# Beetech_NanoEvery.net
KiCad netlist of a schematic drawn in Altium Designer
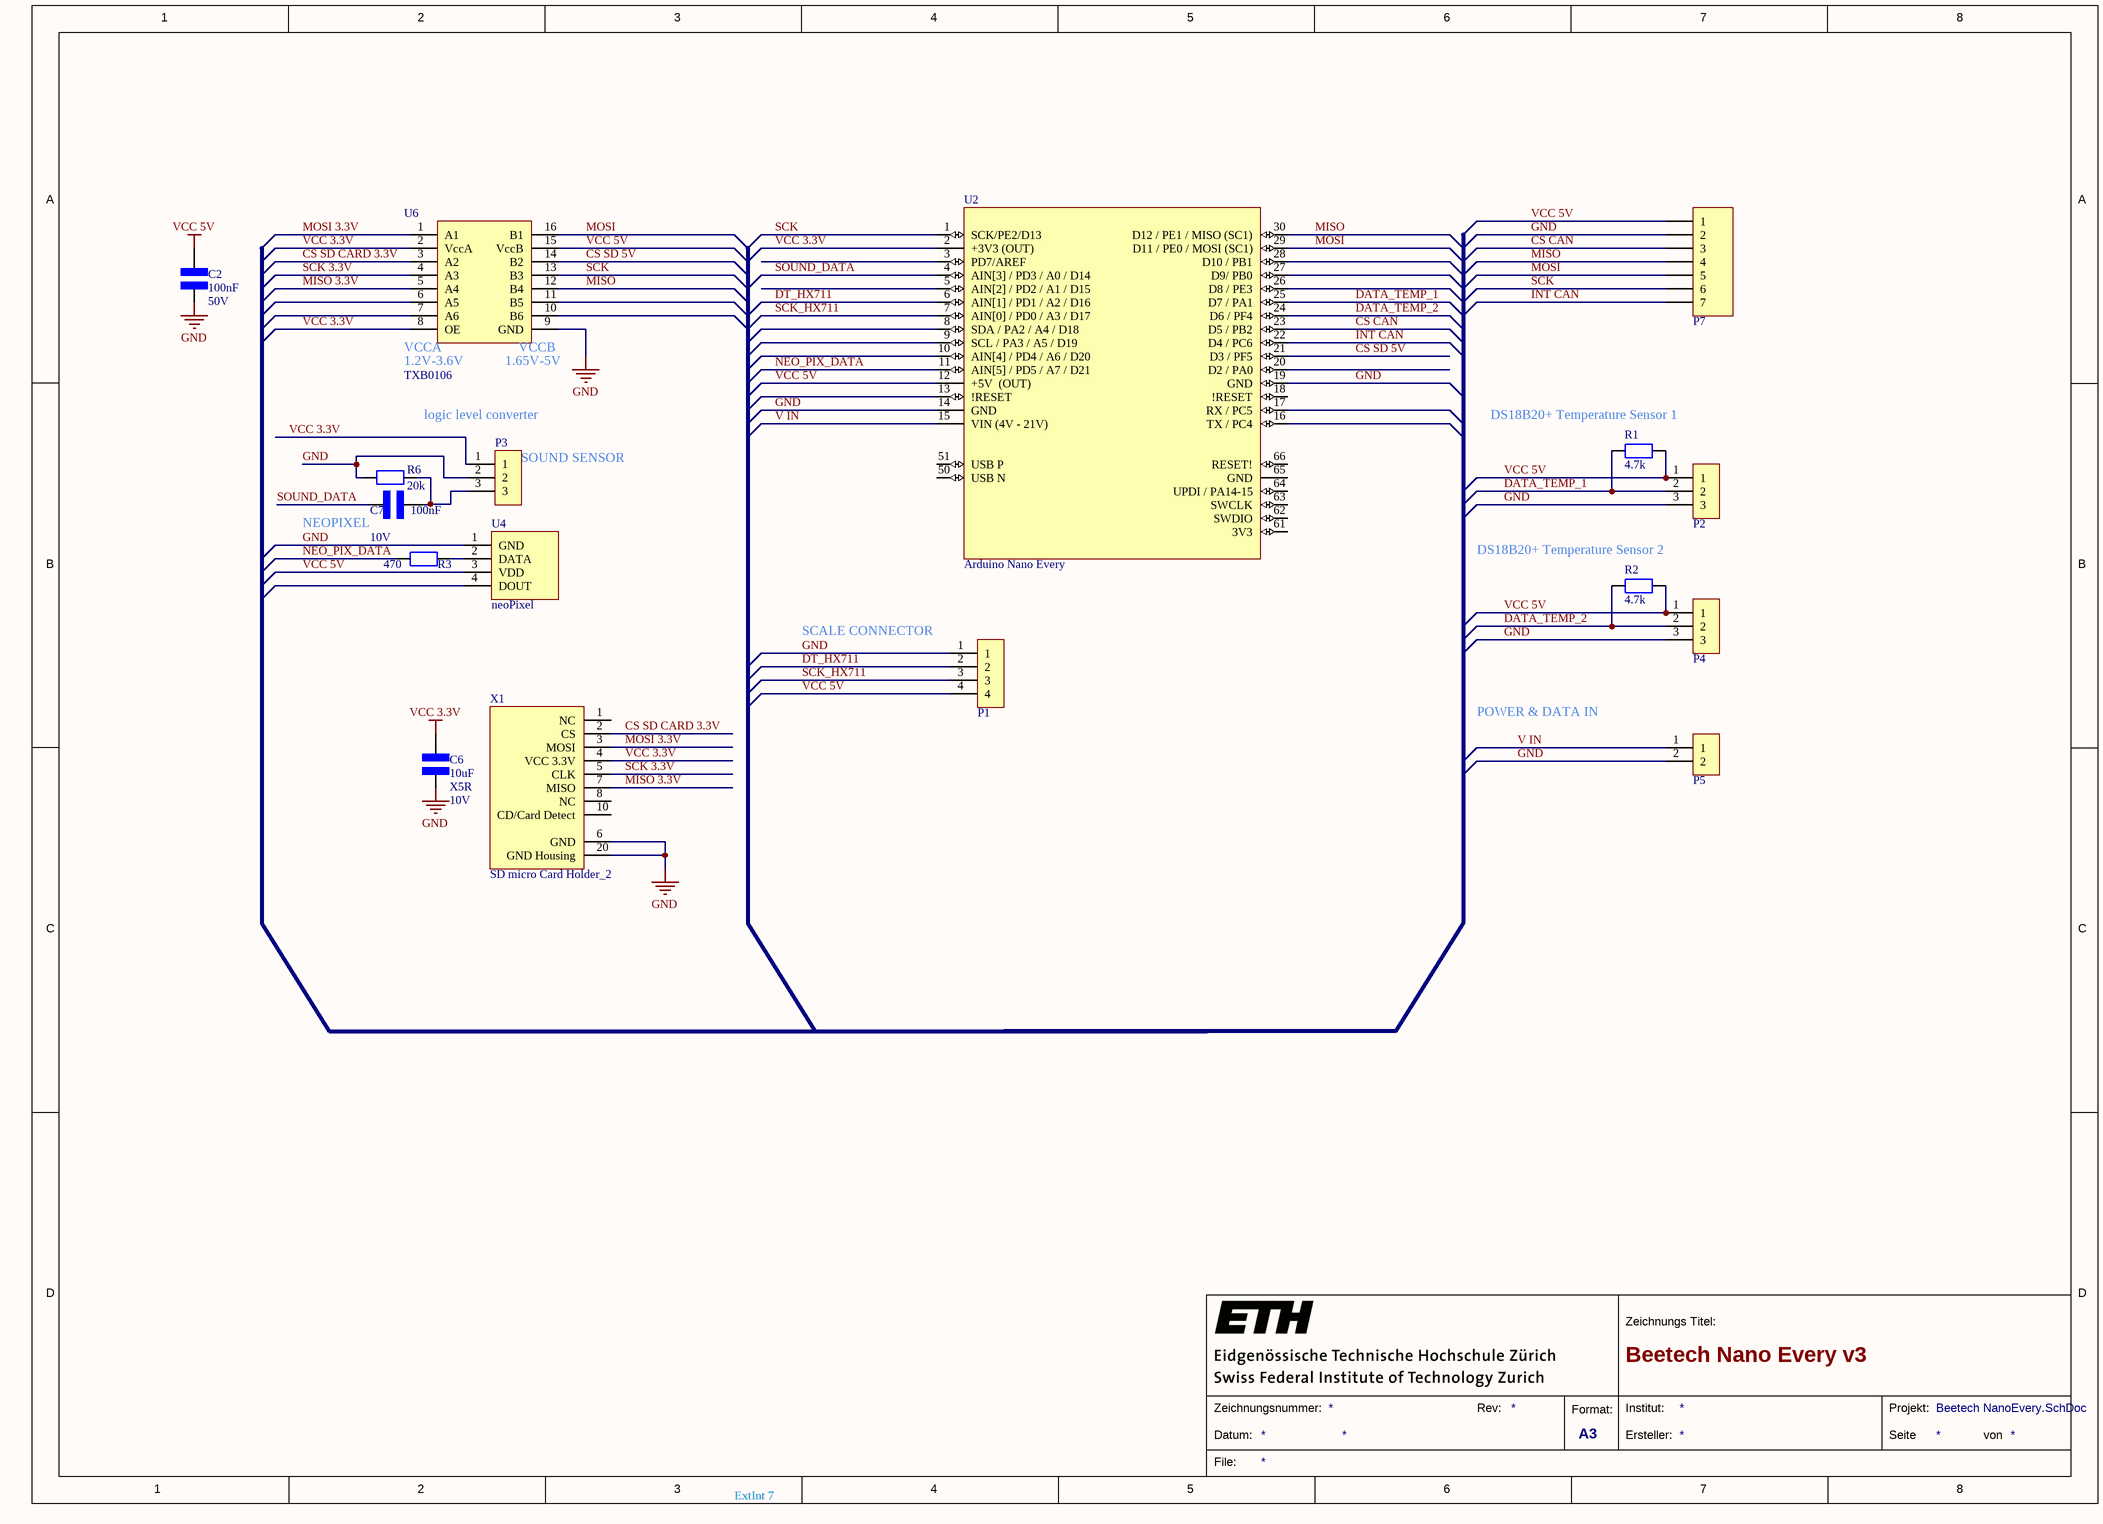
[diagram p0: Beetech NanoEvery.SchDoc]

(export (version "E")
  (design (tool "Eeschema 10.0.6"))
  (components
    (comp (ref "C2")
      (value "100nF")
      (footprint "CAP 0603")
      (description "C CERAMIC SMD")
      (fields (field (name "UMAX") "50V") (field (name "Comment") "100nF 0603_1"))
      (libsource (lib "Library CAP") (part "100nF 0603_1"))
    )
    (comp (ref "C6")
      (value "10uF")
      (footprint "CAP 0603")
      (description "C CERAMIC SMD")
      (fields
        (field (name "DIELEKTRIKUM") "X5R")
        (field (name "UMAX") "10V")
        (field (name "Comment") "10uF 0603")
      )
      (libsource (lib "Library CAP") (part "10uF 0603"))
    )
    (comp (ref "C7")
      (value "100nF")
      (footprint "CAP 0603")
      (description "C CERAMIC SMD")
      (fields (field (name "UMAX") "10V") (field (name "Comment") "100nF 0603"))
      (libsource (lib "Library CAP") (part "100nF 0603"))
    )
    (comp (ref "P1")
      (value "4-Pin Right Angle Housing")
      (footprint "4PIN - RND 205-EK254-2.54-04P")
      (description "4-Pin")
      (libsource (lib "Library Scematic") (part "4-Pin Screw Terminal"))
    )
    (comp (ref "P2")
      (value "3-Pin Right Angle Housing")
      (footprint "3PIN - RND 205-EK254-2.54-03P")
      (description "3-Pin")
      (libsource (lib "Library Scematic") (part "3-Pin Screw Terminal"))
    )
    (comp (ref "P3")
      (value "3-Pin Right Angle Housing")
      (footprint "3PIN - RND 205-EK254-2.54-03P")
      (description "3-Pin")
      (libsource (lib "Library Scematic") (part "3-Pin Screw Terminal"))
    )
    (comp (ref "P4")
      (value "3-Pin Right Angle Housing")
      (footprint "3PIN - RND 205-EK254-2.54-03P")
      (description "3-Pin")
      (libsource (lib "Library Scematic") (part "3-Pin Screw Terminal"))
    )
    (comp (ref "P5")
      (value "2-Pin Right Angle Housing")
      (footprint "2PIN - RND 205-EK254-2.54-02P")
      (description "2-Pin")
      (libsource (lib "Library Scematic") (part "2-Pin Screw Terminal"))
    )
    (comp (ref "P7")
      (value "8-Pin")
      (footprint "7PIN")
      (fields (field (name "PUBLISHER") "Altium Limited"))
      (libsource (lib "Library Scematic") (part "7-Pin"))
    )
    (comp (ref "R1")
      (value "4.7k")
      (footprint "RES 0603 FOOTPRINT")
      (description "R SMD")
      (fields (field (name "Comment") "4.7k Ohm 0603"))
      (libsource (lib "Library RES") (part "4.7k Ohm 0603"))
    )
    (comp (ref "R2")
      (value "4.7k")
      (footprint "RES 0603 FOOTPRINT")
      (description "R SMD")
      (fields (field (name "Comment") "4.7k Ohm 0603"))
      (libsource (lib "Library RES") (part "4.7k Ohm 0603"))
    )
    (comp (ref "R3")
      (value "470")
      (footprint "RES 0603 FOOTPRINT")
      (description "R SMD")
      (fields (field (name "Comment") "470 Ohm 0603"))
      (libsource (lib "Library RES") (part "470 Ohm 0603"))
    )
    (comp (ref "R6")
      (value "20k")
      (footprint "RES 0603 FOOTPRINT")
      (description "R SMD")
      (fields (field (name "Comment") "20k Ohm 0603"))
      (libsource (lib "Library RES") (part "20k Ohm 0603"))
    )
    (comp (ref "U2")
      (value "Arduino Nano Every")
      (footprint "Arduino Nano Every")
      (description "https://store.arduino.cc/nano-every-pack")
      (libsource (lib "Library Scematic") (part "Arduino Nano Every"))
    )
    (comp (ref "U4")
      (value "neoPixel")
      (footprint "neoPixel 5050 adafruit 1655")
      (description "neoPixel 5050 adafruit 1655")
      (libsource (lib "Library Scematic") (part "neoPixel 5050 adafruit 1655"))
    )
    (comp (ref "U6")
      (value "TXB0106")
      (footprint "TSSOP-16L")
      (description "Level Converter TXB0106")
      (libsource (lib "Library Scematic") (part "TXB0106 Level Converter"))
    )
    (comp (ref "X1")
      (value "SD micro Card Holder_2")
      (footprint "SD Card Holder - micro - 2 - sd Card inserted")
      (description "SD micro Card  Holder")
      (libsource (lib "Library Scematic") (part "SD micro Card Holder_2"))
    )
  )
  (nets
    (net (code "1") (name "/CS CAN") (class "Default")
      (node (ref "P7") (pin "3") (pinfunction "3_3") (pintype "passive"))
      (node (ref "U2") (pin "23") (pinfunction "D5_/_PB2_23") (pintype "bidirectional"))
    )
    (net (code "2") (name "/CS SD 5V") (class "Default")
      (node (ref "U2") (pin "21") (pinfunction "D3_/_PF5_21") (pintype "bidirectional"))
      (node (ref "U6") (pin "14") (pinfunction "B2_14") (pintype "passive"))
    )
    (net (code "3") (name "/CS SD CARD 3.3V") (class "Default")
      (node (ref "U6") (pin "3") (pinfunction "A2_3") (pintype "passive"))
      (node (ref "X1") (pin "2") (pinfunction "CS_2") (pintype "passive"))
    )
    (net (code "4") (name "/DATA_TEMP_1") (class "Default")
      (node (ref "P2") (pin "2") (pinfunction "2_2") (pintype "passive"))
      (node (ref "R1") (pin "2") (pinfunction "2_2") (pintype "passive"))
      (node (ref "U2") (pin "25") (pinfunction "D7_/_PA1_25") (pintype "bidirectional"))
    )
    (net (code "5") (name "/DATA_TEMP_2") (class "Default")
      (node (ref "P4") (pin "2") (pinfunction "2_2") (pintype "passive"))
      (node (ref "R2") (pin "2") (pinfunction "2_2") (pintype "passive"))
      (node (ref "U2") (pin "24") (pinfunction "D6_/_PF4_24") (pintype "bidirectional"))
    )
    (net (code "6") (name "/DT_HX711") (class "Default")
      (node (ref "P1") (pin "2") (pinfunction "2_2") (pintype "passive"))
      (node (ref "U2") (pin "6") (pinfunction "AIN[1]_/_PD1_/_A2_/_D16_6") (pintype "bidirectional"))
    )
    (net (code "7") (name "/INT CAN") (class "Default")
      (node (ref "P7") (pin "7") (pinfunction "7_7") (pintype "passive"))
      (node (ref "U2") (pin "22") (pinfunction "D4_/_PC6_22") (pintype "bidirectional"))
    )
    (net (code "8") (name "/MISO") (class "Default")
      (node (ref "P7") (pin "4") (pinfunction "4_4") (pintype "passive"))
      (node (ref "U2") (pin "30") (pinfunction "D12_/_PE1_/_MISO_(SC1)_30") (pintype "bidirectional"))
      (node (ref "U6") (pin "12") (pinfunction "B4_12") (pintype "passive"))
    )
    (net (code "9") (name "/MISO 3.3V") (class "Default")
      (node (ref "U6") (pin "5") (pinfunction "A4_5") (pintype "passive"))
      (node (ref "X1") (pin "7") (pinfunction "MISO_7") (pintype "passive"))
    )
    (net (code "10") (name "/MOSI") (class "Default")
      (node (ref "P7") (pin "5") (pinfunction "5_5") (pintype "passive"))
      (node (ref "U2") (pin "29") (pinfunction "D11_/_PE0_/_MOSI_(SC1)_29") (pintype "bidirectional"))
      (node (ref "U6") (pin "16") (pinfunction "B1_16") (pintype "passive"))
    )
    (net (code "11") (name "/MOSI 3.3V") (class "Default")
      (node (ref "U6") (pin "1") (pinfunction "A1_1") (pintype "power_in"))
      (node (ref "X1") (pin "3") (pinfunction "MOSI_3") (pintype "passive"))
    )
    (net (code "12") (name "/NEO_PIX_DATA") (class "Default")
      (node (ref "R3") (pin "1") (pinfunction "1_1") (pintype "passive"))
      (node (ref "U2") (pin "11") (pinfunction "AIN[5]_/_PD5_/_A7_/_D21_11") (pintype "bidirectional"))
    )
    (net (code "13") (name "/SCK") (class "Default")
      (node (ref "P7") (pin "6") (pinfunction "6_6") (pintype "passive"))
      (node (ref "U2") (pin "1") (pinfunction "SCK/PE2/D13_1") (pintype "bidirectional"))
      (node (ref "U6") (pin "13") (pinfunction "B3_13") (pintype "passive"))
    )
    (net (code "14") (name "/SCK 3.3V") (class "Default")
      (node (ref "U6") (pin "4") (pinfunction "A3_4") (pintype "passive"))
      (node (ref "X1") (pin "5") (pinfunction "CLK_5") (pintype "passive"))
    )
    (net (code "15") (name "/SCK_HX711") (class "Default")
      (node (ref "P1") (pin "3") (pinfunction "3_3") (pintype "passive"))
      (node (ref "U2") (pin "7") (pinfunction "AIN[0]_/_PD0_/_A3_/_D17_7") (pintype "bidirectional"))
    )
    (net (code "16") (name "/SOUND_DATA") (class "Default")
      (node (ref "C7") (pin "1") (pinfunction "1_1") (pintype "passive"))
      (node (ref "U2") (pin "4") (pinfunction "AIN[3]_/_PD3_/_A0_/_D14_4") (pintype "bidirectional"))
    )
    (net (code "17") (name "/V IN") (class "Default")
      (node (ref "P5") (pin "1") (pinfunction "1_1") (pintype "passive"))
      (node (ref "U2") (pin "15") (pinfunction "VIN_(4V_-_21V)_15") (pintype "power_in"))
    )
    (net (code "18") (name "GND") (class "Default")
      (node (ref "C2") (pin "1") (pinfunction "1_1") (pintype "passive"))
      (node (ref "C6") (pin "1") (pinfunction "1_1") (pintype "passive"))
      (node (ref "P1") (pin "1") (pinfunction "1_1") (pintype "passive"))
      (node (ref "P2") (pin "3") (pinfunction "3_3") (pintype "passive"))
      (node (ref "P3") (pin "2") (pinfunction "2_2") (pintype "passive"))
      (node (ref "P4") (pin "3") (pinfunction "3_3") (pintype "passive"))
      (node (ref "P5") (pin "2") (pinfunction "2_2") (pintype "passive"))
      (node (ref "P7") (pin "2") (pinfunction "2_2") (pintype "passive"))
      (node (ref "R6") (pin "1") (pinfunction "1_1") (pintype "passive"))
      (node (ref "U2") (pin "14") (pinfunction "GND_14") (pintype "power_in"))
      (node (ref "U2") (pin "19") (pinfunction "GND_19") (pintype "bidirectional"))
      (node (ref "U4") (pin "1") (pinfunction "GND_1") (pintype "passive"))
      (node (ref "U6") (pin "9") (pinfunction "GND_9") (pintype "passive"))
      (node (ref "X1") (pin "20") (pinfunction "GND_Housing_20") (pintype "passive"))
      (node (ref "X1") (pin "6") (pinfunction "GND_6") (pintype "passive"))
    )
    (net (code "19") (name "Net-(C7-Pad2)") (class "Default")
      (node (ref "C7") (pin "2") (pinfunction "2_2") (pintype "passive"))
      (node (ref "P3") (pin "3") (pinfunction "3_3") (pintype "passive"))
      (node (ref "R6") (pin "2") (pinfunction "2_2") (pintype "passive"))
    )
    (net (code "20") (name "Net-(U4-DATA)") (class "Default")
      (node (ref "R3") (pin "2") (pinfunction "2_2") (pintype "passive"))
      (node (ref "U4") (pin "2") (pinfunction "DATA_2") (pintype "passive"))
    )
    (net (code "21") (name "VCC 3.3V") (class "Default")
      (node (ref "C6") (pin "2") (pinfunction "2_2") (pintype "passive"))
      (node (ref "P3") (pin "1") (pinfunction "1_1") (pintype "passive"))
      (node (ref "U2") (pin "2") (pinfunction "+3V3_(OUT)_2") (pintype "power_in"))
      (node (ref "U6") (pin "2") (pinfunction "VccA_2") (pintype "passive"))
      (node (ref "U6") (pin "8") (pinfunction "OE_8") (pintype "passive"))
      (node (ref "X1") (pin "4") (pinfunction "VCC_3.3V_4") (pintype "passive"))
    )
    (net (code "22") (name "VCC 5V") (class "Default")
      (node (ref "C2") (pin "2") (pinfunction "2_2") (pintype "passive"))
      (node (ref "P1") (pin "4") (pinfunction "4_4") (pintype "passive"))
      (node (ref "P2") (pin "1") (pinfunction "1_1") (pintype "passive"))
      (node (ref "P4") (pin "1") (pinfunction "1_1") (pintype "passive"))
      (node (ref "P7") (pin "1") (pinfunction "1_1") (pintype "passive"))
      (node (ref "R1") (pin "1") (pinfunction "1_1") (pintype "passive"))
      (node (ref "R2") (pin "1") (pinfunction "1_1") (pintype "passive"))
      (node (ref "U2") (pin "12") (pinfunction "+5V__(OUT)_12") (pintype "power_in"))
      (node (ref "U4") (pin "3") (pinfunction "VDD_3") (pintype "passive"))
      (node (ref "U6") (pin "15") (pinfunction "VccB_15") (pintype "passive"))
    )
    (net (code "23") (name "unconnected-(U2-!RESET-Pad13)") (class "Default")
      (node (ref "U2") (pin "13") (pinfunction "!RESET_13") (pintype "bidirectional"))
    )
    (net (code "24") (name "unconnected-(U2-!RESET-Pad18)") (class "Default")
      (node (ref "U2") (pin "18") (pinfunction "!RESET_18") (pintype "bidirectional"))
    )
    (net (code "25") (name "unconnected-(U2-3V3-Pad61)") (class "Default")
      (node (ref "U2") (pin "61") (pinfunction "3V3_61") (pintype "bidirectional"))
    )
    (net (code "26") (name "unconnected-(U2-AIN[2]_{slash}_PD2_{slash}_A1_{slash}_D15-Pad5)") (class "Default")
      (node (ref "U2") (pin "5") (pinfunction "AIN[2]_/_PD2_/_A1_/_D15_5") (pintype "bidirectional"))
    )
    (net (code "27") (name "unconnected-(U2-AIN[4]_{slash}_PD4_{slash}_A6_{slash}_D20-Pad10)") (class "Default")
      (node (ref "U2") (pin "10") (pinfunction "AIN[4]_/_PD4_/_A6_/_D20_10") (pintype "bidirectional"))
    )
    (net (code "28") (name "unconnected-(U2-D2_{slash}_PA0-Pad20)") (class "Default")
      (node (ref "U2") (pin "20") (pinfunction "D2_/_PA0_20") (pintype "bidirectional"))
    )
    (net (code "29") (name "unconnected-(U2-D8_{slash}_PE3-Pad26)") (class "Default")
      (node (ref "U2") (pin "26") (pinfunction "D8_/_PE3_26") (pintype "bidirectional"))
    )
    (net (code "30") (name "unconnected-(U2-D9{slash}_PB0-Pad27)") (class "Default")
      (node (ref "U2") (pin "27") (pinfunction "D9/_PB0_27") (pintype "bidirectional"))
    )
    (net (code "31") (name "unconnected-(U2-D10_{slash}_PB1-Pad28)") (class "Default")
      (node (ref "U2") (pin "28") (pinfunction "D10_/_PB1_28") (pintype "bidirectional"))
    )
    (net (code "32") (name "unconnected-(U2-GND-Pad65)") (class "Default")
      (node (ref "U2") (pin "65") (pinfunction "GND_65") (pintype "power_in"))
    )
    (net (code "33") (name "unconnected-(U2-PD7{slash}AREF-Pad3)") (class "Default")
      (node (ref "U2") (pin "3") (pinfunction "PD7/AREF_3") (pintype "bidirectional"))
    )
    (net (code "34") (name "unconnected-(U2-RESET!-Pad66)") (class "Default")
      (node (ref "U2") (pin "66") (pinfunction "RESET!_66") (pintype "bidirectional"))
    )
    (net (code "35") (name "unconnected-(U2-RX_{slash}_PC5-Pad17)") (class "Default")
      (node (ref "U2") (pin "17") (pinfunction "RX_/_PC5_17") (pintype "bidirectional"))
    )
    (net (code "36") (name "unconnected-(U2-SCL_{slash}_PA3_{slash}_A5_{slash}_D19-Pad9)") (class "Default")
      (node (ref "U2") (pin "9") (pinfunction "SCL_/_PA3_/_A5_/_D19_9") (pintype "bidirectional"))
    )
    (net (code "37") (name "unconnected-(U2-SDA_{slash}_PA2_{slash}_A4_{slash}_D18-Pad8)") (class "Default")
      (node (ref "U2") (pin "8") (pinfunction "SDA_/_PA2_/_A4_/_D18_8") (pintype "bidirectional"))
    )
    (net (code "38") (name "unconnected-(U2-SWCLK-Pad63)") (class "Default")
      (node (ref "U2") (pin "63") (pinfunction "SWCLK_63") (pintype "bidirectional"))
    )
    (net (code "39") (name "unconnected-(U2-SWDIO-Pad62)") (class "Default")
      (node (ref "U2") (pin "62") (pinfunction "SWDIO_62") (pintype "bidirectional"))
    )
    (net (code "40") (name "unconnected-(U2-TX_{slash}_PC4-Pad16)") (class "Default")
      (node (ref "U2") (pin "16") (pinfunction "TX_/_PC4_16") (pintype "bidirectional"))
    )
    (net (code "41") (name "unconnected-(U2-UPDI_{slash}_PA14-15-Pad64)") (class "Default")
      (node (ref "U2") (pin "64") (pinfunction "UPDI_/_PA14-15_64") (pintype "bidirectional"))
    )
    (net (code "42") (name "unconnected-(U2-USB_N-Pad50)") (class "Default")
      (node (ref "U2") (pin "50") (pinfunction "USB_N_50") (pintype "bidirectional"))
    )
    (net (code "43") (name "unconnected-(U2-USB_P-Pad51)") (class "Default")
      (node (ref "U2") (pin "51") (pinfunction "USB_P_51") (pintype "bidirectional"))
    )
    (net (code "44") (name "unconnected-(U4-DOUT-Pad4)") (class "Default")
      (node (ref "U4") (pin "4") (pinfunction "DOUT_4") (pintype "passive"))
    )
    (net (code "45") (name "unconnected-(U6-A5-Pad6)") (class "Default")
      (node (ref "U6") (pin "6") (pinfunction "A5_6") (pintype "passive"))
    )
    (net (code "46") (name "unconnected-(U6-A6-Pad7)") (class "Default")
      (node (ref "U6") (pin "7") (pinfunction "A6_7") (pintype "passive"))
    )
    (net (code "47") (name "unconnected-(U6-B5-Pad11)") (class "Default")
      (node (ref "U6") (pin "11") (pinfunction "B5_11") (pintype "passive"))
    )
    (net (code "48") (name "unconnected-(U6-B6-Pad10)") (class "Default")
      (node (ref "U6") (pin "10") (pinfunction "B6_10") (pintype "passive"))
    )
    (net (code "49") (name "unconnected-(X1-CD{slash}Card_Detect-Pad10)") (class "Default")
      (node (ref "X1") (pin "10") (pinfunction "CD/Card_Detect_10") (pintype "passive"))
    )
    (net (code "50") (name "unconnected-(X1-NC-Pad1)") (class "Default")
      (node (ref "X1") (pin "1") (pinfunction "NC_1") (pintype "passive"))
    )
    (net (code "51") (name "unconnected-(X1-NC-Pad8)") (class "Default")
      (node (ref "X1") (pin "8") (pinfunction "NC_8") (pintype "passive"))
    )
  )
)
